# design.net
KiCad netlist of a schematic drawn in Altium Designer
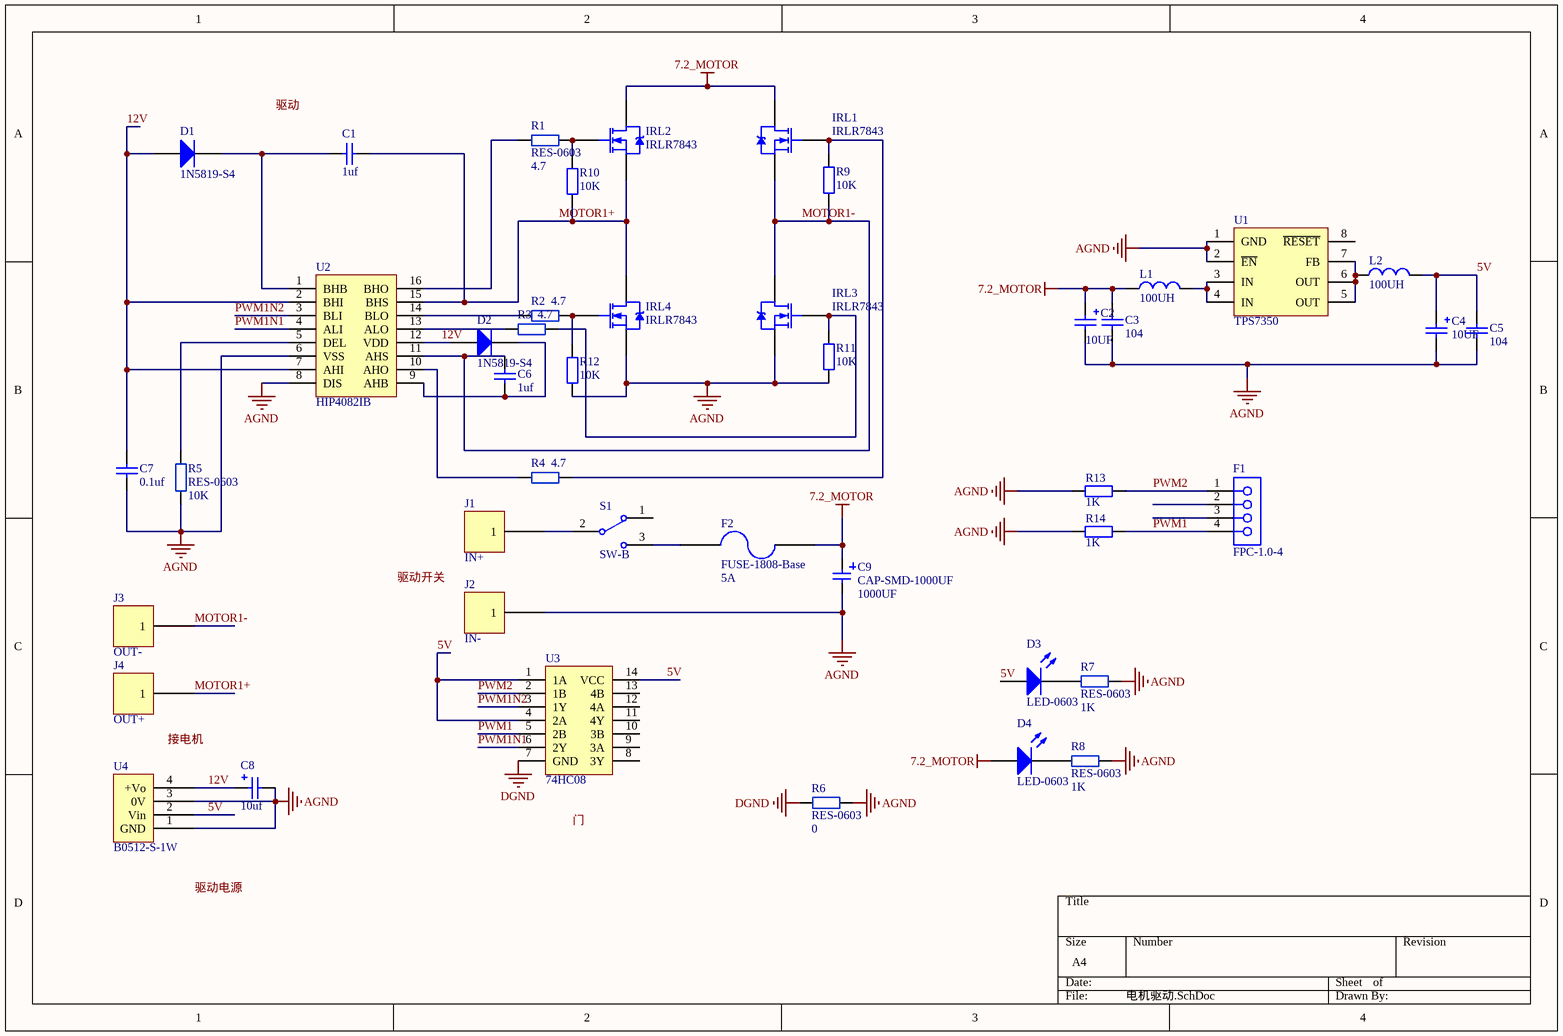
[diagram p0: 电机驱动.SchDoc]

(export (version "E")
  (design (tool "Eeschema 10.0.6"))
  (components
    (comp (ref "C1")
      (value "CAP-0603(1608)")
      (footprint "CAP-0603")
      (fields (field (name "ALTIUM_UNNAMED_1") "1uf"))
      (libsource (lib "Common_zlh") (part "CAP-0603(1608)"))
    )
    (comp (ref "C2")
      (value "CAP-TAN-3528(B)")
      (footprint "CAP-3528")
      (description "0.15~150UF")
      (fields (field (name "ALTIUM_UNNAMED_1") "10UF"))
      (libsource (lib "Common_zlh") (part "CAP-TAN-3528(B)"))
    )
    (comp (ref "C3")
      (value "CAP-0603(1608)")
      (footprint "CAP-0603")
      (fields (field (name "ALTIUM_UNNAMED_1") "104"))
      (libsource (lib "Common_zlh") (part "CAP-0603(1608)"))
    )
    (comp (ref "C4")
      (value "CAP-TAN-3528(B)")
      (footprint "CAP-3528")
      (description "0.15~150UF")
      (fields (field (name "ALTIUM_UNNAMED_1") "10UF"))
      (libsource (lib "Common_zlh") (part "CAP-TAN-3528(B)"))
    )
    (comp (ref "C5")
      (value "CAP-0603(1608)")
      (footprint "CAP-0603")
      (fields (field (name "ALTIUM_UNNAMED_1") "104"))
      (libsource (lib "Common_zlh") (part "CAP-0603(1608)"))
    )
    (comp (ref "C6")
      (value "CAP-0603(1608)")
      (footprint "CAP-0603")
      (fields (field (name "ALTIUM_UNNAMED_1") "1uf"))
      (libsource (lib "Common_zlh") (part "CAP-0603(1608)"))
    )
    (comp (ref "C7")
      (value "CAP-0603(1608)")
      (footprint "CAP-0603")
      (fields (field (name "ALTIUM_UNNAMED_1") "0.1uf"))
      (libsource (lib "Common_zlh") (part "CAP-0603(1608)"))
    )
    (comp (ref "C8")
      (value "CAP-TAN-3528(B)")
      (footprint "CAP-3528")
      (description "0.15~150UF")
      (fields (field (name "ALTIUM_UNNAMED_1") "10uf"))
      (libsource (lib "Common_zlh") (part "CAP-TAN-3528(B)"))
    )
    (comp (ref "C9")
      (value "CAP-SMD-1000UF")
      (footprint "CAP-SMD-1000UF")
      (fields (field (name "ALTIUM_UNNAMED_1") "1000UF"))
      (libsource (lib "lw_commom") (part "CAP-SMD-1000UF"))
    )
    (comp (ref "D1")
      (value "1N5819-S4")
      (footprint "SOD-323")
      (description "S4")
      (libsource (lib "Common_zlh") (part "1N5819-S4"))
    )
    (comp (ref "D2")
      (value "1N5819-S4")
      (footprint "SOD-323")
      (description "S4")
      (libsource (lib "Common_zlh") (part "1N5819-S4"))
    )
    (comp (ref "D3")
      (value "LED-0603")
      (footprint "LED-0603")
      (libsource (lib "Common_zlh") (part "LED-0603"))
    )
    (comp (ref "D4")
      (value "LED-0603")
      (footprint "LED-0603")
      (libsource (lib "Common_zlh") (part "LED-0603"))
    )
    (comp (ref "F1")
      (value "FPC-1.0-4")
      (footprint "FPC-1.0-4")
      (libsource (lib "Connector_zlh") (part "FPC-1.0-4"))
    )
    (comp (ref "F2")
      (value "FUSE-1808-Base")
      (footprint "Fuse1808_Base")
      (description "保险丝")
      (fields (field (name "ALTIUM_UNNAMED_1") "5A"))
      (libsource (lib "Common_zlh") (part "FUSE-1808-Base"))
    )
    (comp (ref "IRL1") (value "IRLR7843") (footprint "TO-252") (libsource (lib "IC_zlh") (part "IRLR7843")))
    (comp (ref "IRL2") (value "IRLR7843") (footprint "TO-252") (libsource (lib "IC_zlh") (part "IRLR7843")))
    (comp (ref "IRL3") (value "IRLR7843") (footprint "TO-252") (libsource (lib "IC_zlh") (part "IRLR7843")))
    (comp (ref "IRL4") (value "IRLR7843") (footprint "TO-252") (libsource (lib "IC_zlh") (part "IRLR7843")))
    (comp (ref "J1")
      (value "IN+")
      (footprint "HEADER1X1")
      (libsource (lib "lw_connecter") (part "Header1x1"))
    )
    (comp (ref "J2")
      (value "IN-")
      (footprint "HEADER1X1")
      (libsource (lib "lw_connecter") (part "Header1x1"))
    )
    (comp (ref "J3")
      (value "OUT-")
      (footprint "HEADER1X1")
      (libsource (lib "lw_connecter") (part "Header1x1"))
    )
    (comp (ref "J4")
      (value "OUT+")
      (footprint "HEADER1X1")
      (libsource (lib "lw_connecter") (part "Header1x1"))
    )
    (comp (ref "L1")
      (value "INTUCTOR")
      (footprint "L0805 - duplicate")
      (fields (field (name "ALTIUM_UNNAMED_1") "100UH"))
      (libsource (lib "天行者主驱") (part "INTUCTOR"))
    )
    (comp (ref "L2")
      (value "INTUCTOR")
      (footprint "L0805 - duplicate")
      (fields (field (name "ALTIUM_UNNAMED_1") "100UH"))
      (libsource (lib "天行者主驱") (part "INTUCTOR"))
    )
    (comp (ref "R1")
      (value "RES-0603")
      (footprint "RES-0603")
      (fields (field (name "ALTIUM_UNNAMED_1") "4.7"))
      (libsource (lib "Common_zlh") (part "RES-0603"))
    )
    (comp (ref "R2")
      (value "RES-0603")
      (footprint "RES-0603")
      (fields (field (name "ALTIUM_UNNAMED_1") "4.7"))
      (libsource (lib "Common_zlh") (part "RES-0603"))
    )
    (comp (ref "R3")
      (value "RES-0603")
      (footprint "RES-0603")
      (fields (field (name "ALTIUM_UNNAMED_1") "4.7"))
      (libsource (lib "Common_zlh") (part "RES-0603"))
    )
    (comp (ref "R4")
      (value "RES-0603")
      (footprint "RES-0603")
      (fields (field (name "ALTIUM_UNNAMED_1") "4.7"))
      (libsource (lib "Common_zlh") (part "RES-0603"))
    )
    (comp (ref "R5")
      (value "RES-0603")
      (footprint "RES-0603")
      (fields (field (name "ALTIUM_UNNAMED_1") "10K"))
      (libsource (lib "Common_zlh") (part "RES-0603"))
    )
    (comp (ref "R6")
      (value "RES-0603")
      (footprint "RES-0603")
      (fields (field (name "ALTIUM_UNNAMED_1") "0"))
      (libsource (lib "Common_zlh") (part "RES-0603"))
    )
    (comp (ref "R7")
      (value "RES-0603")
      (footprint "RES-0603")
      (fields (field (name "ALTIUM_UNNAMED_1") "1K"))
      (libsource (lib "Common_zlh") (part "RES-0603"))
    )
    (comp (ref "R8")
      (value "RES-0603")
      (footprint "RES-0603")
      (fields (field (name "ALTIUM_UNNAMED_1") "1K"))
      (libsource (lib "Common_zlh") (part "RES-0603"))
    )
    (comp (ref "R9")
      (value "RES")
      (footprint "0603RC")
      (fields (field (name "ALTIUM_UNNAMED_1") "10K"))
      (libsource (lib "天行者主驱") (part "RES"))
    )
    (comp (ref "R10")
      (value "RES")
      (footprint "0603RC")
      (fields (field (name "ALTIUM_UNNAMED_1") "10K"))
      (libsource (lib "天行者主驱") (part "RES"))
    )
    (comp (ref "R11")
      (value "RES")
      (footprint "0603RC")
      (fields (field (name "ALTIUM_UNNAMED_1") "10K"))
      (libsource (lib "天行者主驱") (part "RES"))
    )
    (comp (ref "R12")
      (value "RES")
      (footprint "0603RC")
      (fields (field (name "ALTIUM_UNNAMED_1") "10K"))
      (libsource (lib "天行者主驱") (part "RES"))
    )
    (comp (ref "R13")
      (value "1K")
      (footprint "0603RC")
      (description "Resistor")
      (fields (field (name "PUBLISHER") "Altium Limited"))
      (libsource (lib "天行者主驱") (part "Res2"))
    )
    (comp (ref "R14")
      (value "1K")
      (footprint "0603RC")
      (description "Resistor")
      (fields (field (name "PUBLISHER") "Altium Limited"))
      (libsource (lib "天行者主驱") (part "Res2"))
    )
    (comp (ref "S1") (value "SW-B") (footprint "SW-B") (libsource (lib "lw_common") (part "SW-B")))
    (comp (ref "U1") (value "TPS7350") (footprint "TPS7350(7333)") (libsource (lib "天行者主驱") (part "TPS7350")))
    (comp (ref "U2") (value "HIP4082IB") (footprint "SOIC16") (libsource (lib "IC_zlh") (part "HIP4082IB")))
    (comp (ref "U3") (value "74HC08") (footprint "SOIC14") (libsource (lib "IC_zlh") (part "74HC08")))
    (comp (ref "U4")
      (value "B0512-S-1W")
      (footprint "B0512_S_1W")
      (libsource (lib "IC_zlh") (part "B0512-S-1W"))
    )
  )
  (nets
    (net (code "1") (name "/5V") (class "Default")
      (node (ref "C4") (pin "1") (pinfunction "1_1") (pintype "passive"))
      (node (ref "C5") (pin "2") (pinfunction "2_2") (pintype "passive"))
      (node (ref "D3") (pin "1") (pinfunction "A_1") (pintype "passive"))
      (node (ref "L2") (pin "2") (pinfunction "2_2") (pintype "passive"))
      (node (ref "U3") (pin "1") (pinfunction "1A_1") (pintype "passive"))
      (node (ref "U3") (pin "14") (pinfunction "VCC_14") (pintype "passive"))
      (node (ref "U3") (pin "4") (pinfunction "2A_4") (pintype "passive"))
      (node (ref "U4") (pin "2") (pinfunction "Vin_2") (pintype "passive"))
    )
    (net (code "2") (name "/12V") (class "Default")
      (node (ref "C7") (pin "2") (pinfunction "2_2") (pintype "passive"))
      (node (ref "C8") (pin "1") (pinfunction "1_1") (pintype "passive"))
      (node (ref "D1") (pin "1") (pinfunction "A_1") (pintype "passive"))
      (node (ref "D2") (pin "1") (pinfunction "A_1") (pintype "passive"))
      (node (ref "U2") (pin "12") (pinfunction "VDD_12") (pintype "passive"))
      (node (ref "U2") (pin "2") (pinfunction "BHI_2") (pintype "passive"))
      (node (ref "U2") (pin "7") (pinfunction "AHI_7") (pintype "passive"))
      (node (ref "U4") (pin "4") (pinfunction "+Vo_4") (pintype "passive"))
    )
    (net (code "3") (name "/MOTOR1+") (class "Default")
      (node (ref "C1") (pin "2") (pinfunction "2_2") (pintype "passive"))
      (node (ref "IRL2") (pin "3") (pinfunction "S_3") (pintype "passive"))
      (node (ref "IRL4") (pin "2") (pinfunction "D_2") (pintype "passive"))
      (node (ref "J4") (pin "1") (pinfunction "1_1") (pintype "passive"))
      (node (ref "R10") (pin "1") (pinfunction "1_1") (pintype "passive"))
      (node (ref "U2") (pin "15") (pinfunction "BHS_15") (pintype "passive"))
    )
    (net (code "4") (name "/MOTOR1-") (class "Default")
      (node (ref "C6") (pin "2") (pinfunction "2_2") (pintype "passive"))
      (node (ref "IRL1") (pin "3") (pinfunction "S_3") (pintype "passive"))
      (node (ref "IRL3") (pin "2") (pinfunction "D_2") (pintype "passive"))
      (node (ref "J3") (pin "1") (pinfunction "1_1") (pintype "passive"))
      (node (ref "R9") (pin "1") (pinfunction "1_1") (pintype "passive"))
      (node (ref "U2") (pin "11") (pinfunction "AHS_11") (pintype "passive"))
    )
    (net (code "5") (name "/PWM1") (class "Default")
      (node (ref "F1") (pin "4") (pinfunction "4_4") (pintype "passive"))
      (node (ref "R14") (pin "2") (pinfunction "2_2") (pintype "passive"))
      (node (ref "U3") (pin "5") (pinfunction "2B_5") (pintype "passive"))
    )
    (net (code "6") (name "/PWM1N1") (class "Default")
      (node (ref "U2") (pin "4") (pinfunction "ALI_4") (pintype "passive"))
      (node (ref "U3") (pin "6") (pinfunction "2Y_6") (pintype "passive"))
    )
    (net (code "7") (name "/PWM1N2") (class "Default")
      (node (ref "U2") (pin "3") (pinfunction "BLI_3") (pintype "passive"))
      (node (ref "U3") (pin "3") (pinfunction "1Y_3") (pintype "passive"))
    )
    (net (code "8") (name "/PWM2") (class "Default")
      (node (ref "F1") (pin "1") (pinfunction "1_1") (pintype "passive"))
      (node (ref "R13") (pin "2") (pinfunction "2_2") (pintype "passive"))
      (node (ref "U3") (pin "2") (pinfunction "1B_2") (pintype "passive"))
    )
    (net (code "14") (name "7.2_MOTOR") (class "Default")
      (node (ref "C2") (pin "1") (pinfunction "1_1") (pintype "passive"))
      (node (ref "C3") (pin "2") (pinfunction "2_2") (pintype "passive"))
      (node (ref "C9") (pin "1") (pinfunction "1_1") (pintype "passive"))
      (node (ref "D4") (pin "1") (pinfunction "A_1") (pintype "passive"))
      (node (ref "F2") (pin "2") (pinfunction "2_2") (pintype "passive"))
      (node (ref "IRL1") (pin "2") (pinfunction "D_2") (pintype "passive"))
      (node (ref "IRL2") (pin "2") (pinfunction "D_2") (pintype "passive"))
      (node (ref "L1") (pin "1") (pinfunction "1_1") (pintype "passive"))
    )
    (net (code "15") (name "AGND") (class "Default")
      (node (ref "C2") (pin "2") (pinfunction "2_2") (pintype "passive"))
      (node (ref "C3") (pin "1") (pinfunction "1_1") (pintype "passive"))
      (node (ref "C4") (pin "2") (pinfunction "2_2") (pintype "passive"))
      (node (ref "C5") (pin "1") (pinfunction "1_1") (pintype "passive"))
      (node (ref "C7") (pin "1") (pinfunction "1_1") (pintype "passive"))
      (node (ref "C8") (pin "2") (pinfunction "2_2") (pintype "passive"))
      (node (ref "C9") (pin "2") (pinfunction "2_2") (pintype "passive"))
      (node (ref "IRL3") (pin "3") (pinfunction "S_3") (pintype "passive"))
      (node (ref "IRL4") (pin "3") (pinfunction "S_3") (pintype "passive"))
      (node (ref "J2") (pin "1") (pinfunction "1_1") (pintype "passive"))
      (node (ref "R11") (pin "1") (pinfunction "1_1") (pintype "passive"))
      (node (ref "R12") (pin "1") (pinfunction "1_1") (pintype "passive"))
      (node (ref "R13") (pin "1") (pinfunction "1_1") (pintype "passive"))
      (node (ref "R14") (pin "1") (pinfunction "1_1") (pintype "passive"))
      (node (ref "R5") (pin "1") (pinfunction "1_1") (pintype "passive"))
      (node (ref "R6") (pin "2") (pinfunction "2_2") (pintype "passive"))
      (node (ref "R7") (pin "2") (pinfunction "2_2") (pintype "passive"))
      (node (ref "R8") (pin "2") (pinfunction "2_2") (pintype "passive"))
      (node (ref "U1") (pin "1") (pinfunction "GND_1") (pintype "power_in"))
      (node (ref "U1") (pin "2") (pinfunction "~{EN}_2") (pintype "power_in"))
      (node (ref "U2") (pin "6") (pinfunction "VSS_6") (pintype "passive"))
      (node (ref "U2") (pin "8") (pinfunction "DIS_8") (pintype "passive"))
      (node (ref "U4") (pin "1") (pinfunction "GND_1") (pintype "passive"))
      (node (ref "U4") (pin "3") (pinfunction "0V_3") (pintype "passive"))
    )
    (net (code "16") (name "DGND") (class "Default")
      (node (ref "R6") (pin "1") (pinfunction "1_1") (pintype "passive"))
      (node (ref "U3") (pin "7") (pinfunction "GND_7") (pintype "passive"))
    )
    (net (code "17") (name "Net-(D1-K)") (class "Default")
      (node (ref "C1") (pin "1") (pinfunction "1_1") (pintype "passive"))
      (node (ref "D1") (pin "2") (pinfunction "K_2") (pintype "passive"))
      (node (ref "U2") (pin "1") (pinfunction "BHB_1") (pintype "passive"))
    )
    (net (code "18") (name "Net-(D2-K)") (class "Default")
      (node (ref "C6") (pin "1") (pinfunction "1_1") (pintype "passive"))
      (node (ref "D2") (pin "2") (pinfunction "K_2") (pintype "passive"))
      (node (ref "U2") (pin "9") (pinfunction "AHB_9") (pintype "passive"))
    )
    (net (code "19") (name "Net-(D3-K)") (class "Default")
      (node (ref "D3") (pin "2") (pinfunction "K_2") (pintype "passive"))
      (node (ref "R7") (pin "1") (pinfunction "1_1") (pintype "passive"))
    )
    (net (code "20") (name "Net-(D4-K)") (class "Default")
      (node (ref "D4") (pin "2") (pinfunction "K_2") (pintype "passive"))
      (node (ref "R8") (pin "1") (pinfunction "1_1") (pintype "passive"))
    )
    (net (code "21") (name "Net-(F2-Pad1)") (class "Default")
      (node (ref "F2") (pin "1") (pinfunction "1_1") (pintype "passive"))
      (node (ref "S1") (pin "3") (pinfunction "3_3") (pintype "passive"))
    )
    (net (code "22") (name "Net-(IRL1-G)") (class "Default")
      (node (ref "IRL1") (pin "1") (pinfunction "G_1") (pintype "passive"))
      (node (ref "R4") (pin "2") (pinfunction "2_2") (pintype "passive"))
      (node (ref "R9") (pin "2") (pinfunction "2_2") (pintype "passive"))
    )
    (net (code "23") (name "Net-(IRL2-G)") (class "Default")
      (node (ref "IRL2") (pin "1") (pinfunction "G_1") (pintype "passive"))
      (node (ref "R1") (pin "2") (pinfunction "2_2") (pintype "passive"))
      (node (ref "R10") (pin "2") (pinfunction "2_2") (pintype "passive"))
    )
    (net (code "24") (name "Net-(IRL3-G)") (class "Default")
      (node (ref "IRL3") (pin "1") (pinfunction "G_1") (pintype "passive"))
      (node (ref "R11") (pin "2") (pinfunction "2_2") (pintype "passive"))
      (node (ref "R3") (pin "2") (pinfunction "2_2") (pintype "passive"))
    )
    (net (code "25") (name "Net-(IRL4-G)") (class "Default")
      (node (ref "IRL4") (pin "1") (pinfunction "G_1") (pintype "passive"))
      (node (ref "R12") (pin "2") (pinfunction "2_2") (pintype "passive"))
      (node (ref "R2") (pin "2") (pinfunction "2_2") (pintype "passive"))
    )
    (net (code "26") (name "Net-(J1-Pad1)") (class "Default")
      (node (ref "J1") (pin "1") (pinfunction "1_1") (pintype "passive"))
      (node (ref "S1") (pin "2") (pinfunction "2_2") (pintype "passive"))
    )
    (net (code "27") (name "Net-(L1-Pad2)") (class "Default")
      (node (ref "L1") (pin "2") (pinfunction "2_2") (pintype "passive"))
      (node (ref "U1") (pin "3") (pinfunction "IN_3") (pintype "power_in"))
      (node (ref "U1") (pin "4") (pinfunction "IN_4") (pintype "power_in"))
    )
    (net (code "28") (name "Net-(U1-FB)") (class "Default")
      (node (ref "L2") (pin "1") (pinfunction "1_1") (pintype "passive"))
      (node (ref "U1") (pin "5") (pinfunction "OUT_5") (pintype "power_in"))
      (node (ref "U1") (pin "6") (pinfunction "OUT_6") (pintype "power_in"))
      (node (ref "U1") (pin "7") (pinfunction "FB_7") (pintype "power_in"))
    )
    (net (code "29") (name "Net-(U2-AHO)") (class "Default")
      (node (ref "R4") (pin "1") (pinfunction "1_1") (pintype "passive"))
      (node (ref "U2") (pin "10") (pinfunction "AHO_10") (pintype "passive"))
    )
    (net (code "30") (name "Net-(U2-ALO)") (class "Default")
      (node (ref "R3") (pin "1") (pinfunction "1_1") (pintype "passive"))
      (node (ref "U2") (pin "13") (pinfunction "ALO_13") (pintype "passive"))
    )
    (net (code "31") (name "Net-(U2-BHO)") (class "Default")
      (node (ref "R1") (pin "1") (pinfunction "1_1") (pintype "passive"))
      (node (ref "U2") (pin "16") (pinfunction "BHO_16") (pintype "passive"))
    )
    (net (code "32") (name "Net-(U2-BLO)") (class "Default")
      (node (ref "R2") (pin "1") (pinfunction "1_1") (pintype "passive"))
      (node (ref "U2") (pin "14") (pinfunction "BLO_14") (pintype "passive"))
    )
    (net (code "33") (name "Net-(U2-DEL)") (class "Default")
      (node (ref "R5") (pin "2") (pinfunction "2_2") (pintype "passive"))
      (node (ref "U2") (pin "5") (pinfunction "DEL_5") (pintype "passive"))
    )
    (net (code "34") (name "unconnected-(F1-Pad2)") (class "Default")
      (node (ref "F1") (pin "2") (pinfunction "2_2") (pintype "passive"))
    )
    (net (code "35") (name "unconnected-(F1-Pad3)") (class "Default")
      (node (ref "F1") (pin "3") (pinfunction "3_3") (pintype "passive"))
    )
    (net (code "36") (name "unconnected-(S1-Pad1)") (class "Default")
      (node (ref "S1") (pin "1") (pinfunction "1_1") (pintype "passive"))
    )
    (net (code "37") (name "unconnected-(U1-~{RESET}-Pad8)") (class "Default")
      (node (ref "U1") (pin "8") (pinfunction "~{RESET}_8") (pintype "power_in"))
    )
    (net (code "38") (name "unconnected-(U3-3A-Pad9)") (class "Default")
      (node (ref "U3") (pin "9") (pinfunction "3A_9") (pintype "passive"))
    )
    (net (code "39") (name "unconnected-(U3-3B-Pad10)") (class "Default")
      (node (ref "U3") (pin "10") (pinfunction "3B_10") (pintype "passive"))
    )
    (net (code "40") (name "unconnected-(U3-3Y-Pad8)") (class "Default")
      (node (ref "U3") (pin "8") (pinfunction "3Y_8") (pintype "passive"))
    )
    (net (code "41") (name "unconnected-(U3-4A-Pad12)") (class "Default")
      (node (ref "U3") (pin "12") (pinfunction "4A_12") (pintype "passive"))
    )
    (net (code "42") (name "unconnected-(U3-4B-Pad13)") (class "Default")
      (node (ref "U3") (pin "13") (pinfunction "4B_13") (pintype "passive"))
    )
    (net (code "43") (name "unconnected-(U3-4Y-Pad11)") (class "Default")
      (node (ref "U3") (pin "11") (pinfunction "4Y_11") (pintype "passive"))
    )
  )
)
